# SpW_protection.net
KiCad netlist of a schematic drawn in Altium Designer
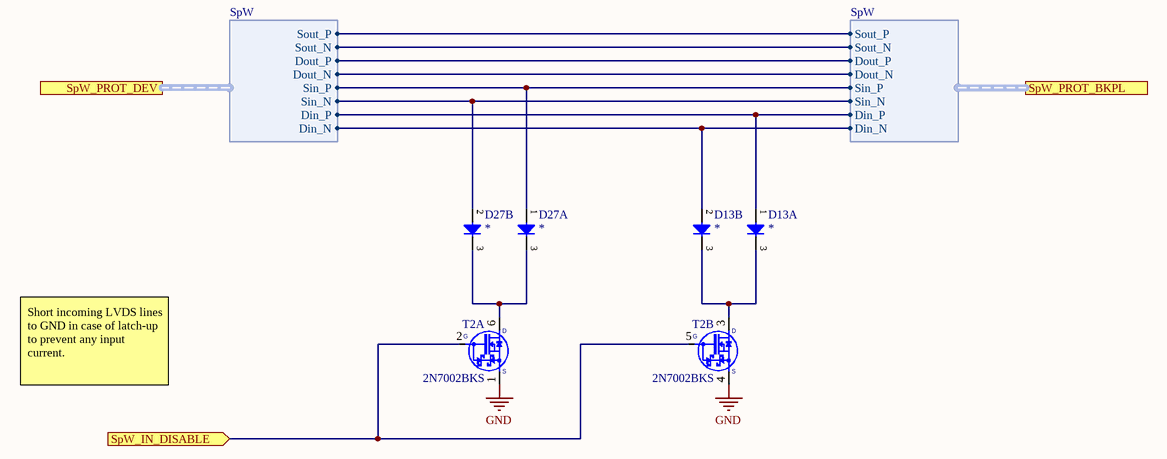
[diagram p0: SpW_protection.SchDoc]

(export (version "E")
  (design (tool "Eeschema 10.0.6"))
  (components
    (comp (ref "D13")
      (value "*")
      (footprint "SOT65P210X110-3N")
      (fields (field (name "MANUFACTURER PART NUMBER") "BAT1705WH6327"))
      (libsource (lib "ICs_And_Semiconductors") (part "BAT1705WH"))
    )
    (comp (ref "D27")
      (value "*")
      (footprint "SOT65P210X110-3N")
      (fields (field (name "MANUFACTURER PART NUMBER") "BAT1705WH6327"))
      (libsource (lib "ICs_And_Semiconductors") (part "BAT1705WH"))
    )
    (comp (ref "T2")
      (value "2N7002BKS")
      (footprint "SOT65P210X110-6N")
      (description "60V, 300mA Dual N-Channel Trench MOSFET")
      (fields
        (field (name "MANUFACTURER") "NXP SEMICONDUCTORS")
        (field (name "MANUFACTURER PART NUMBER") "2N7002BKS6")
        (field (name "AUTHOR") "CERN DEM JLC")
      )
      (libsource (lib "ICs And Semiconductors") (part "2N7002BKS"))
    )
  )
  (nets
    (net (code "2") (name "/Din_N") (class "Default")
      (node (ref "D13") (pin "2") (pinfunction "A_2") (pintype "passive"))
    )
    (net (code "3") (name "/Din_P") (class "Default")
      (node (ref "D13") (pin "1") (pinfunction "A_1") (pintype "passive"))
    )
    (net (code "6") (name "/Sin_N") (class "Default")
      (node (ref "D27") (pin "2") (pinfunction "A_2") (pintype "passive"))
    )
    (net (code "7") (name "/Sin_P") (class "Default")
      (node (ref "D27") (pin "1") (pinfunction "A_1") (pintype "passive"))
    )
    (net (code "10") (name "/SpW_IN_DISABLE") (class "Default")
      (node (ref "T2") (pin "2") (pinfunction "G_2") (pintype "passive"))
      (node (ref "T2") (pin "5") (pinfunction "G_5") (pintype "passive"))
    )
    (net (code "12") (name "GND") (class "Default")
      (node (ref "T2") (pin "1") (pinfunction "S_1") (pintype "passive"))
      (node (ref "T2") (pin "4") (pinfunction "S_4") (pintype "passive"))
    )
    (net (code "13") (name "Net-(D13A-COMC)") (class "Default")
      (node (ref "D13") (pin "3") (pinfunction "COMC_3") (pintype "passive"))
      (node (ref "T2") (pin "3") (pinfunction "D_3") (pintype "passive"))
    )
    (net (code "14") (name "Net-(D27A-COMC)") (class "Default")
      (node (ref "D27") (pin "3") (pinfunction "COMC_3") (pintype "passive"))
      (node (ref "T2") (pin "6") (pinfunction "D_6") (pintype "passive"))
    )
  )
)
